# reciever.net
KiCad netlist of a schematic drawn in EAGLE
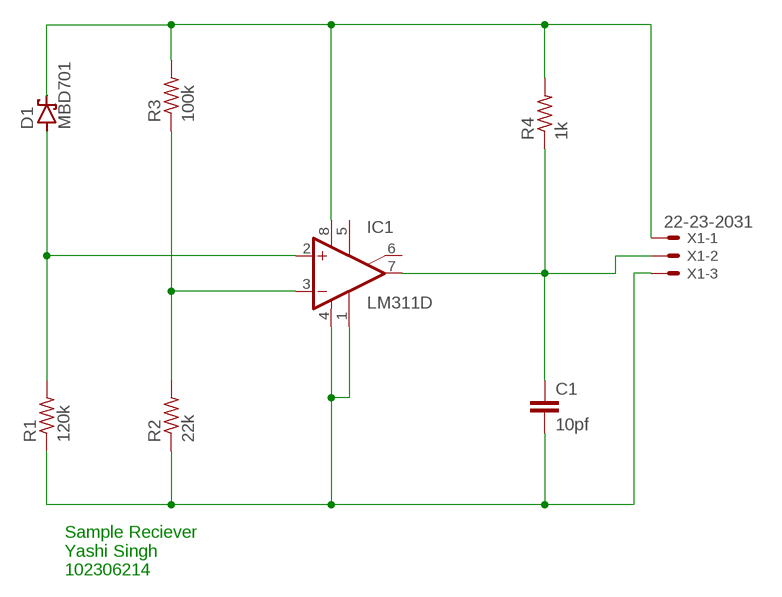
[diagram p0: schematic, sheet 1]

(export (version "E")
  (design (tool "Eeschema 10.0.6"))
  (components
    (comp (ref "C1")
      (value "10pf")
      (footprint "eagle-import:C2.5-2")
      (libsource (lib "eagle-import") (part "C2.5/2"))
    )
    (comp (ref "D1")
      (value "MBD701")
      (footprint "eagle-import:TO92H")
      (libsource (lib "eagle-import") (part "MBD701"))
    )
    (comp (ref "IC1")
      (value "LM311D")
      (footprint "eagle-import:SO08")
      (libsource (lib "eagle-import") (part "LM311D"))
    )
    (comp (ref "R1")
      (value "120k")
      (footprint "eagle-import:0207_10")
      (libsource (lib "eagle-import") (part "R-US_0207/10"))
    )
    (comp (ref "R2")
      (value "22k")
      (footprint "eagle-import:0207_10")
      (libsource (lib "eagle-import") (part "R-US_0207/10"))
    )
    (comp (ref "R3")
      (value "100k")
      (footprint "eagle-import:0207_10")
      (libsource (lib "eagle-import") (part "R-US_0207/10"))
    )
    (comp (ref "R4")
      (value "1k")
      (footprint "eagle-import:0207_10")
      (libsource (lib "eagle-import") (part "R-US_0207/10"))
    )
    (comp (ref "X1")
      (value "22-23-2031")
      (footprint "eagle-import:22-23-2031")
      (fields (field (name "MF") "MOLEX"))
      (libsource (lib "eagle-import") (part "22-23-2031"))
    )
  )
  (nets
    (net (code "1") (name "Net-(D1-A)") (class "Default")
      (node (ref "D1") (pin "1") (pinfunction "A_1") (pintype "passive"))
      (node (ref "IC1") (pin "2") (pinfunction "+IN_2") (pintype "input"))
      (node (ref "R1") (pin "2") (pinfunction "2_2") (pintype "passive"))
    )
    (net (code "2") (name "Net-(D1-C)") (class "Default")
      (node (ref "D1") (pin "2") (pinfunction "C_2") (pintype "passive"))
      (node (ref "IC1") (pin "8") (pinfunction "V+_8") (pintype "power_in"))
      (node (ref "R3") (pin "2") (pinfunction "2_2") (pintype "passive"))
      (node (ref "R4") (pin "2") (pinfunction "2_2") (pintype "passive"))
      (node (ref "X1") (pin "1") (pinfunction "S_1") (pintype "passive"))
    )
    (net (code "3") (name "Net-(IC1--IN)") (class "Default")
      (node (ref "IC1") (pin "3") (pinfunction "-IN_3") (pintype "input"))
      (node (ref "R2") (pin "2") (pinfunction "2_2") (pintype "passive"))
      (node (ref "R3") (pin "1") (pinfunction "1_1") (pintype "passive"))
    )
    (net (code "4") (name "Net-(IC1-GND)") (class "Default")
      (node (ref "C1") (pin "2") (pinfunction "2_2") (pintype "passive"))
      (node (ref "IC1") (pin "1") (pinfunction "GND_1") (pintype "passive"))
      (node (ref "IC1") (pin "4") (pinfunction "V-_4") (pintype "power_in"))
      (node (ref "R1") (pin "1") (pinfunction "1_1") (pintype "passive"))
      (node (ref "R2") (pin "1") (pinfunction "1_1") (pintype "passive"))
      (node (ref "X1") (pin "3") (pinfunction "S_3") (pintype "passive"))
    )
    (net (code "5") (name "Net-(IC1-OUT)") (class "Default")
      (node (ref "C1") (pin "1") (pinfunction "1_1") (pintype "passive"))
      (node (ref "IC1") (pin "7") (pinfunction "OUT_7") (pintype "output"))
      (node (ref "R4") (pin "1") (pinfunction "1_1") (pintype "passive"))
      (node (ref "X1") (pin "2") (pinfunction "S_2") (pintype "passive"))
    )
    (net (code "6") (name "unconnected-(IC1-ON-Pad5)") (class "Default")
      (node (ref "IC1") (pin "5") (pinfunction "ON_5") (pintype "passive"))
    )
    (net (code "7") (name "unconnected-(IC1-ON{slash}STR-Pad6)") (class "Default")
      (node (ref "IC1") (pin "6") (pinfunction "ON/STR_6") (pintype "passive"))
    )
  )
)
